# PortSplitters.net
KiCad netlist of a schematic drawn in Altium Designer
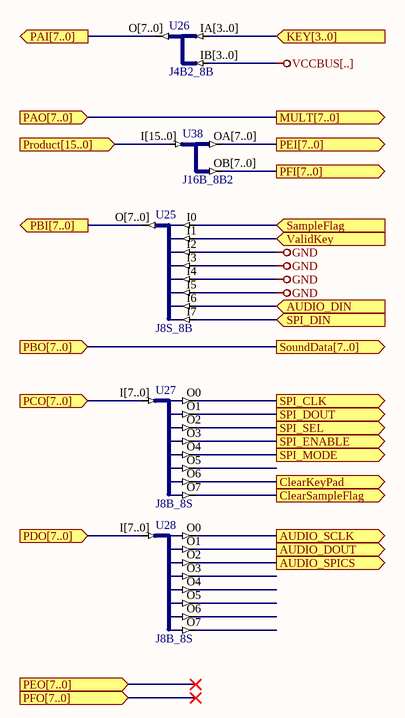
[diagram p0: PortSplitters.SchDoc]

(export (version "E")
  (design (tool "Eeschema 10.0.6"))
  (components
    (comp (ref "U25")
      (value "J8S_8B")
      (description "8 Single pin inputs to single 8-Bit output bus")
      (fields (field (name "PUBLISHER") "Altium Limited"))
      (libsource (lib "FPGA Generic") (part "J8S_8B"))
    )
    (comp (ref "U26")
      (value "J4B2_8B")
      (description "2 x 4-Bit input bus to 1 x 8-bit output bus")
      (fields (field (name "PUBLISHER") "Altium Limited"))
      (libsource (lib "FPGA Generic") (part "J4B2_8B"))
    )
    (comp (ref "U27")
      (value "J8B_8S")
      (description "8-Bit input bus to 8 single pin outputs")
      (fields (field (name "PUBLISHER") "Altium Limited"))
      (libsource (lib "FPGA Generic") (part "J8B_8S"))
    )
    (comp (ref "U28")
      (value "J8B_8S")
      (description "8-Bit input bus to 8 single pin outputs")
      (fields (field (name "PUBLISHER") "Altium Limited"))
      (libsource (lib "FPGA Generic") (part "J8B_8S"))
    )
    (comp (ref "U38")
      (value "J16B_8B2")
      (description "1 x 16-bit input bus to 2 x 8-Bit output bus")
      (fields (field (name "PUBLISHER") "Altium Limited"))
      (libsource (lib "FPGA Generic") (part "J16B_8B2"))
    )
  )
  (nets
    (net (code "101") (name "/AUDIO_DIN") (class "Default")
      (node (ref "U25") (pin "I6") (pinfunction "I6_I6") (pintype "input"))
    )
    (net (code "102") (name "/AUDIO_DOUT") (class "Default")
      (node (ref "U28") (pin "O1") (pinfunction "O1_O1") (pintype "output"))
    )
    (net (code "103") (name "/AUDIO_SCLK") (class "Default")
      (node (ref "U28") (pin "O0") (pinfunction "O0_O0") (pintype "output"))
    )
    (net (code "104") (name "/AUDIO_SPICS") (class "Default")
      (node (ref "U28") (pin "O2") (pinfunction "O2_O2") (pintype "output"))
    )
    (net (code "105") (name "/ClearKeyPad") (class "Default")
      (node (ref "U27") (pin "O6") (pinfunction "O6_O6") (pintype "output"))
    )
    (net (code "106") (name "/ClearSampleFlag") (class "Default")
      (node (ref "U27") (pin "O7") (pinfunction "O7_O7") (pintype "output"))
    )
    (net (code "107") (name "/KEY[3..0]") (class "Default")
      (node (ref "U26") (pin "IA[3..0]") (pinfunction "IA[3..0]_IA[3..0]") (pintype "input"))
    )
    (net (code "109") (name "/PAI[7..0]") (class "Default")
      (node (ref "U26") (pin "O[7..0]") (pinfunction "O[7..0]_O[7..0]") (pintype "output"))
    )
    (net (code "110") (name "/PBI[7..0]") (class "Default")
      (node (ref "U25") (pin "O[7..0]") (pinfunction "O[7..0]_O[7..0]") (pintype "output"))
    )
    (net (code "112") (name "/PCO[7..0]") (class "Default")
      (node (ref "U27") (pin "I[7..0]") (pinfunction "I[7..0]_I[7..0]") (pintype "input"))
    )
    (net (code "113") (name "/PDO[7..0]") (class "Default")
      (node (ref "U28") (pin "I[7..0]") (pinfunction "I[7..0]_I[7..0]") (pintype "input"))
    )
    (net (code "114") (name "/PEI[7..0]") (class "Default")
      (node (ref "U38") (pin "OA[7..0]") (pinfunction "OA[7..0]_OA[7..0]") (pintype "output"))
    )
    (net (code "116") (name "/PFI[7..0]") (class "Default")
      (node (ref "U38") (pin "OB[7..0]") (pinfunction "OB[7..0]_OB[7..0]") (pintype "output"))
    )
    (net (code "118") (name "/Product[15..0]") (class "Default")
      (node (ref "U38") (pin "I[15..0]") (pinfunction "I[15..0]_I[15..0]") (pintype "input"))
    )
    (net (code "119") (name "/SPI_CLK") (class "Default")
      (node (ref "U27") (pin "O0") (pinfunction "O0_O0") (pintype "output"))
    )
    (net (code "120") (name "/SPI_DIN") (class "Default")
      (node (ref "U25") (pin "I7") (pinfunction "I7_I7") (pintype "input"))
    )
    (net (code "121") (name "/SPI_DOUT") (class "Default")
      (node (ref "U27") (pin "O1") (pinfunction "O1_O1") (pintype "output"))
    )
    (net (code "122") (name "/SPI_ENABLE") (class "Default")
      (node (ref "U27") (pin "O3") (pinfunction "O3_O3") (pintype "output"))
    )
    (net (code "123") (name "/SPI_MODE") (class "Default")
      (node (ref "U27") (pin "O4") (pinfunction "O4_O4") (pintype "output"))
    )
    (net (code "124") (name "/SPI_SEL") (class "Default")
      (node (ref "U27") (pin "O2") (pinfunction "O2_O2") (pintype "output"))
    )
    (net (code "125") (name "/SampleFlag") (class "Default")
      (node (ref "U25") (pin "I0") (pinfunction "I0_I0") (pintype "input"))
    )
    (net (code "126") (name "/ValidKey") (class "Default")
      (node (ref "U25") (pin "I1") (pinfunction "I1_I1") (pintype "input"))
    )
    (net (code "127") (name "GND") (class "Default")
      (node (ref "U25") (pin "I2") (pinfunction "I2_I2") (pintype "input"))
      (node (ref "U25") (pin "I3") (pinfunction "I3_I3") (pintype "input"))
      (node (ref "U25") (pin "I4") (pinfunction "I4_I4") (pintype "input"))
      (node (ref "U25") (pin "I5") (pinfunction "I5_I5") (pintype "input"))
    )
    (net (code "128") (name "VCCBUS[..]") (class "Default")
      (node (ref "U26") (pin "IB[3..0]") (pinfunction "IB[3..0]_IB[3..0]") (pintype "input"))
    )
    (net (code "129") (name "unconnected-(U27-PadO5)") (class "Default")
      (node (ref "U27") (pin "O5") (pinfunction "O5_O5") (pintype "output"))
    )
    (net (code "130") (name "unconnected-(U28-PadO3)") (class "Default")
      (node (ref "U28") (pin "O3") (pinfunction "O3_O3") (pintype "output"))
    )
    (net (code "131") (name "unconnected-(U28-PadO4)") (class "Default")
      (node (ref "U28") (pin "O4") (pinfunction "O4_O4") (pintype "output"))
    )
    (net (code "132") (name "unconnected-(U28-PadO5)") (class "Default")
      (node (ref "U28") (pin "O5") (pinfunction "O5_O5") (pintype "output"))
    )
    (net (code "133") (name "unconnected-(U28-PadO6)") (class "Default")
      (node (ref "U28") (pin "O6") (pinfunction "O6_O6") (pintype "output"))
    )
    (net (code "134") (name "unconnected-(U28-PadO7)") (class "Default")
      (node (ref "U28") (pin "O7") (pinfunction "O7_O7") (pintype "output"))
    )
  )
)
